# ekomigacz.net
KiCad netlist of a schematic drawn in EAGLE
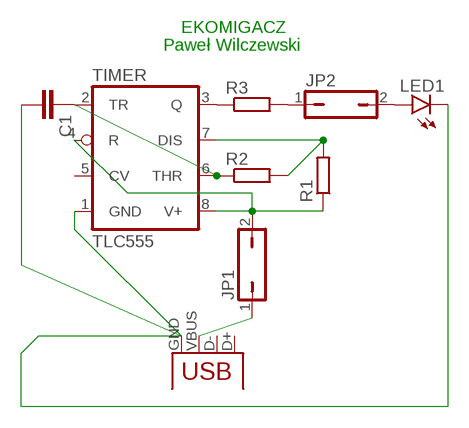
[diagram p0: schematic, sheet 1]

(export (version "E")
  (design (tool "Eeschema 10.0.6"))
  (components
    (comp (ref "C1")
      (value "C5/3")
      (footprint "eagle-import:C5B3")
      (libsource (lib "eagle-import") (part "C5/3"))
    )
    (comp (ref "JP1")
      (value "JP1Q")
      (footprint "eagle-import:JP1")
      (libsource (lib "eagle-import") (part "JP1Q"))
    )
    (comp (ref "JP2")
      (value "JP1Q")
      (footprint "eagle-import:JP1")
      (libsource (lib "eagle-import") (part "JP1Q"))
    )
    (comp (ref "LED1")
      (value "LED5MM")
      (footprint "eagle-import:LED5MM")
      (libsource (lib "eagle-import") (part "LED5MM"))
    )
    (comp (ref "R1")
      (value "R-EU_0207/10")
      (footprint "eagle-import:0207_10")
      (libsource (lib "eagle-import") (part "R-EU_0207/10"))
    )
    (comp (ref "R2")
      (value "R-EU_0207/10")
      (footprint "eagle-import:0207_10")
      (libsource (lib "eagle-import") (part "R-EU_0207/10"))
    )
    (comp (ref "R3")
      (value "R-EU_0207/10")
      (footprint "eagle-import:0207_10")
      (libsource (lib "eagle-import") (part "R-EU_0207/10"))
    )
    (comp (ref "TIMER")
      (value "TLC555")
      (footprint "eagle-import:DIL08")
      (fields (field (name "SPICEPREFIX") "X"))
      (libsource (lib "eagle-import") (part "555NNE"))
    )
    (comp (ref "X1")
      (value "USB-A-H")
      (footprint "eagle-import:USB-A-H")
      (libsource (lib "eagle-import") (part "USB-A-H"))
    )
  )
  (nets
    (net (code "1") (name "Net-(JP1-Pad1)") (class "Default")
      (node (ref "JP1") (pin "1") (pinfunction "1_1") (pintype "passive"))
      (node (ref "X1") (pin "VBUS") (pinfunction "VBUS_VBUS") (pintype "bidirectional"))
    )
    (net (code "2") (name "Net-(JP2-Pad1)") (class "Default")
      (node (ref "JP2") (pin "1") (pinfunction "1_1") (pintype "passive"))
      (node (ref "R3") (pin "2") (pinfunction "2_2") (pintype "passive"))
    )
    (net (code "3") (name "Net-(JP2-Pad2)") (class "Default")
      (node (ref "JP2") (pin "2") (pinfunction "2_2") (pintype "passive"))
      (node (ref "LED1") (pin "A") (pinfunction "A_A") (pintype "passive"))
    )
    (net (code "4") (name "Net-(LED1-C)") (class "Default")
      (node (ref "C1") (pin "2") (pinfunction "2_2") (pintype "passive"))
      (node (ref "LED1") (pin "K") (pinfunction "C_K") (pintype "passive"))
      (node (ref "TIMER") (pin "1") (pinfunction "GND_1") (pintype "power_in"))
      (node (ref "X1") (pin "GND") (pinfunction "GND_GND") (pintype "bidirectional"))
    )
    (net (code "5") (name "Net-(TIMER-DIS)") (class "Default")
      (node (ref "R1") (pin "2") (pinfunction "2_2") (pintype "passive"))
      (node (ref "R2") (pin "2") (pinfunction "2_2") (pintype "passive"))
      (node (ref "TIMER") (pin "7") (pinfunction "DIS_7") (pintype "input"))
    )
    (net (code "6") (name "Net-(TIMER-Q)") (class "Default")
      (node (ref "R3") (pin "1") (pinfunction "1_1") (pintype "passive"))
      (node (ref "TIMER") (pin "3") (pinfunction "Q_3") (pintype "output"))
    )
    (net (code "7") (name "Net-(TIMER-R)") (class "Default")
      (node (ref "JP1") (pin "2") (pinfunction "2_2") (pintype "passive"))
      (node (ref "R1") (pin "1") (pinfunction "1_1") (pintype "passive"))
      (node (ref "TIMER") (pin "4") (pinfunction "R_4") (pintype "input"))
      (node (ref "TIMER") (pin "8") (pinfunction "V+_8") (pintype "power_in"))
    )
    (net (code "8") (name "Net-(TIMER-THR)") (class "Default")
      (node (ref "C1") (pin "1") (pinfunction "1_1") (pintype "passive"))
      (node (ref "R2") (pin "1") (pinfunction "1_1") (pintype "passive"))
      (node (ref "TIMER") (pin "2") (pinfunction "TR_2") (pintype "input"))
      (node (ref "TIMER") (pin "6") (pinfunction "THR_6") (pintype "input"))
    )
    (net (code "9") (name "unconnected-(TIMER-CV-Pad5)") (class "Default")
      (node (ref "TIMER") (pin "5") (pinfunction "CV_5") (pintype "input"))
    )
    (net (code "10") (name "unconnected-(X1-PadD+)") (class "Default")
      (node (ref "X1") (pin "D+") (pinfunction "D+_D+") (pintype "bidirectional"))
    )
    (net (code "11") (name "unconnected-(X1-PadD-)") (class "Default")
      (node (ref "X1") (pin "D-") (pinfunction "D-_D-") (pintype "bidirectional"))
    )
  )
)
